# GBE1_PHY.net
KiCad netlist of a schematic drawn in Altium Designer
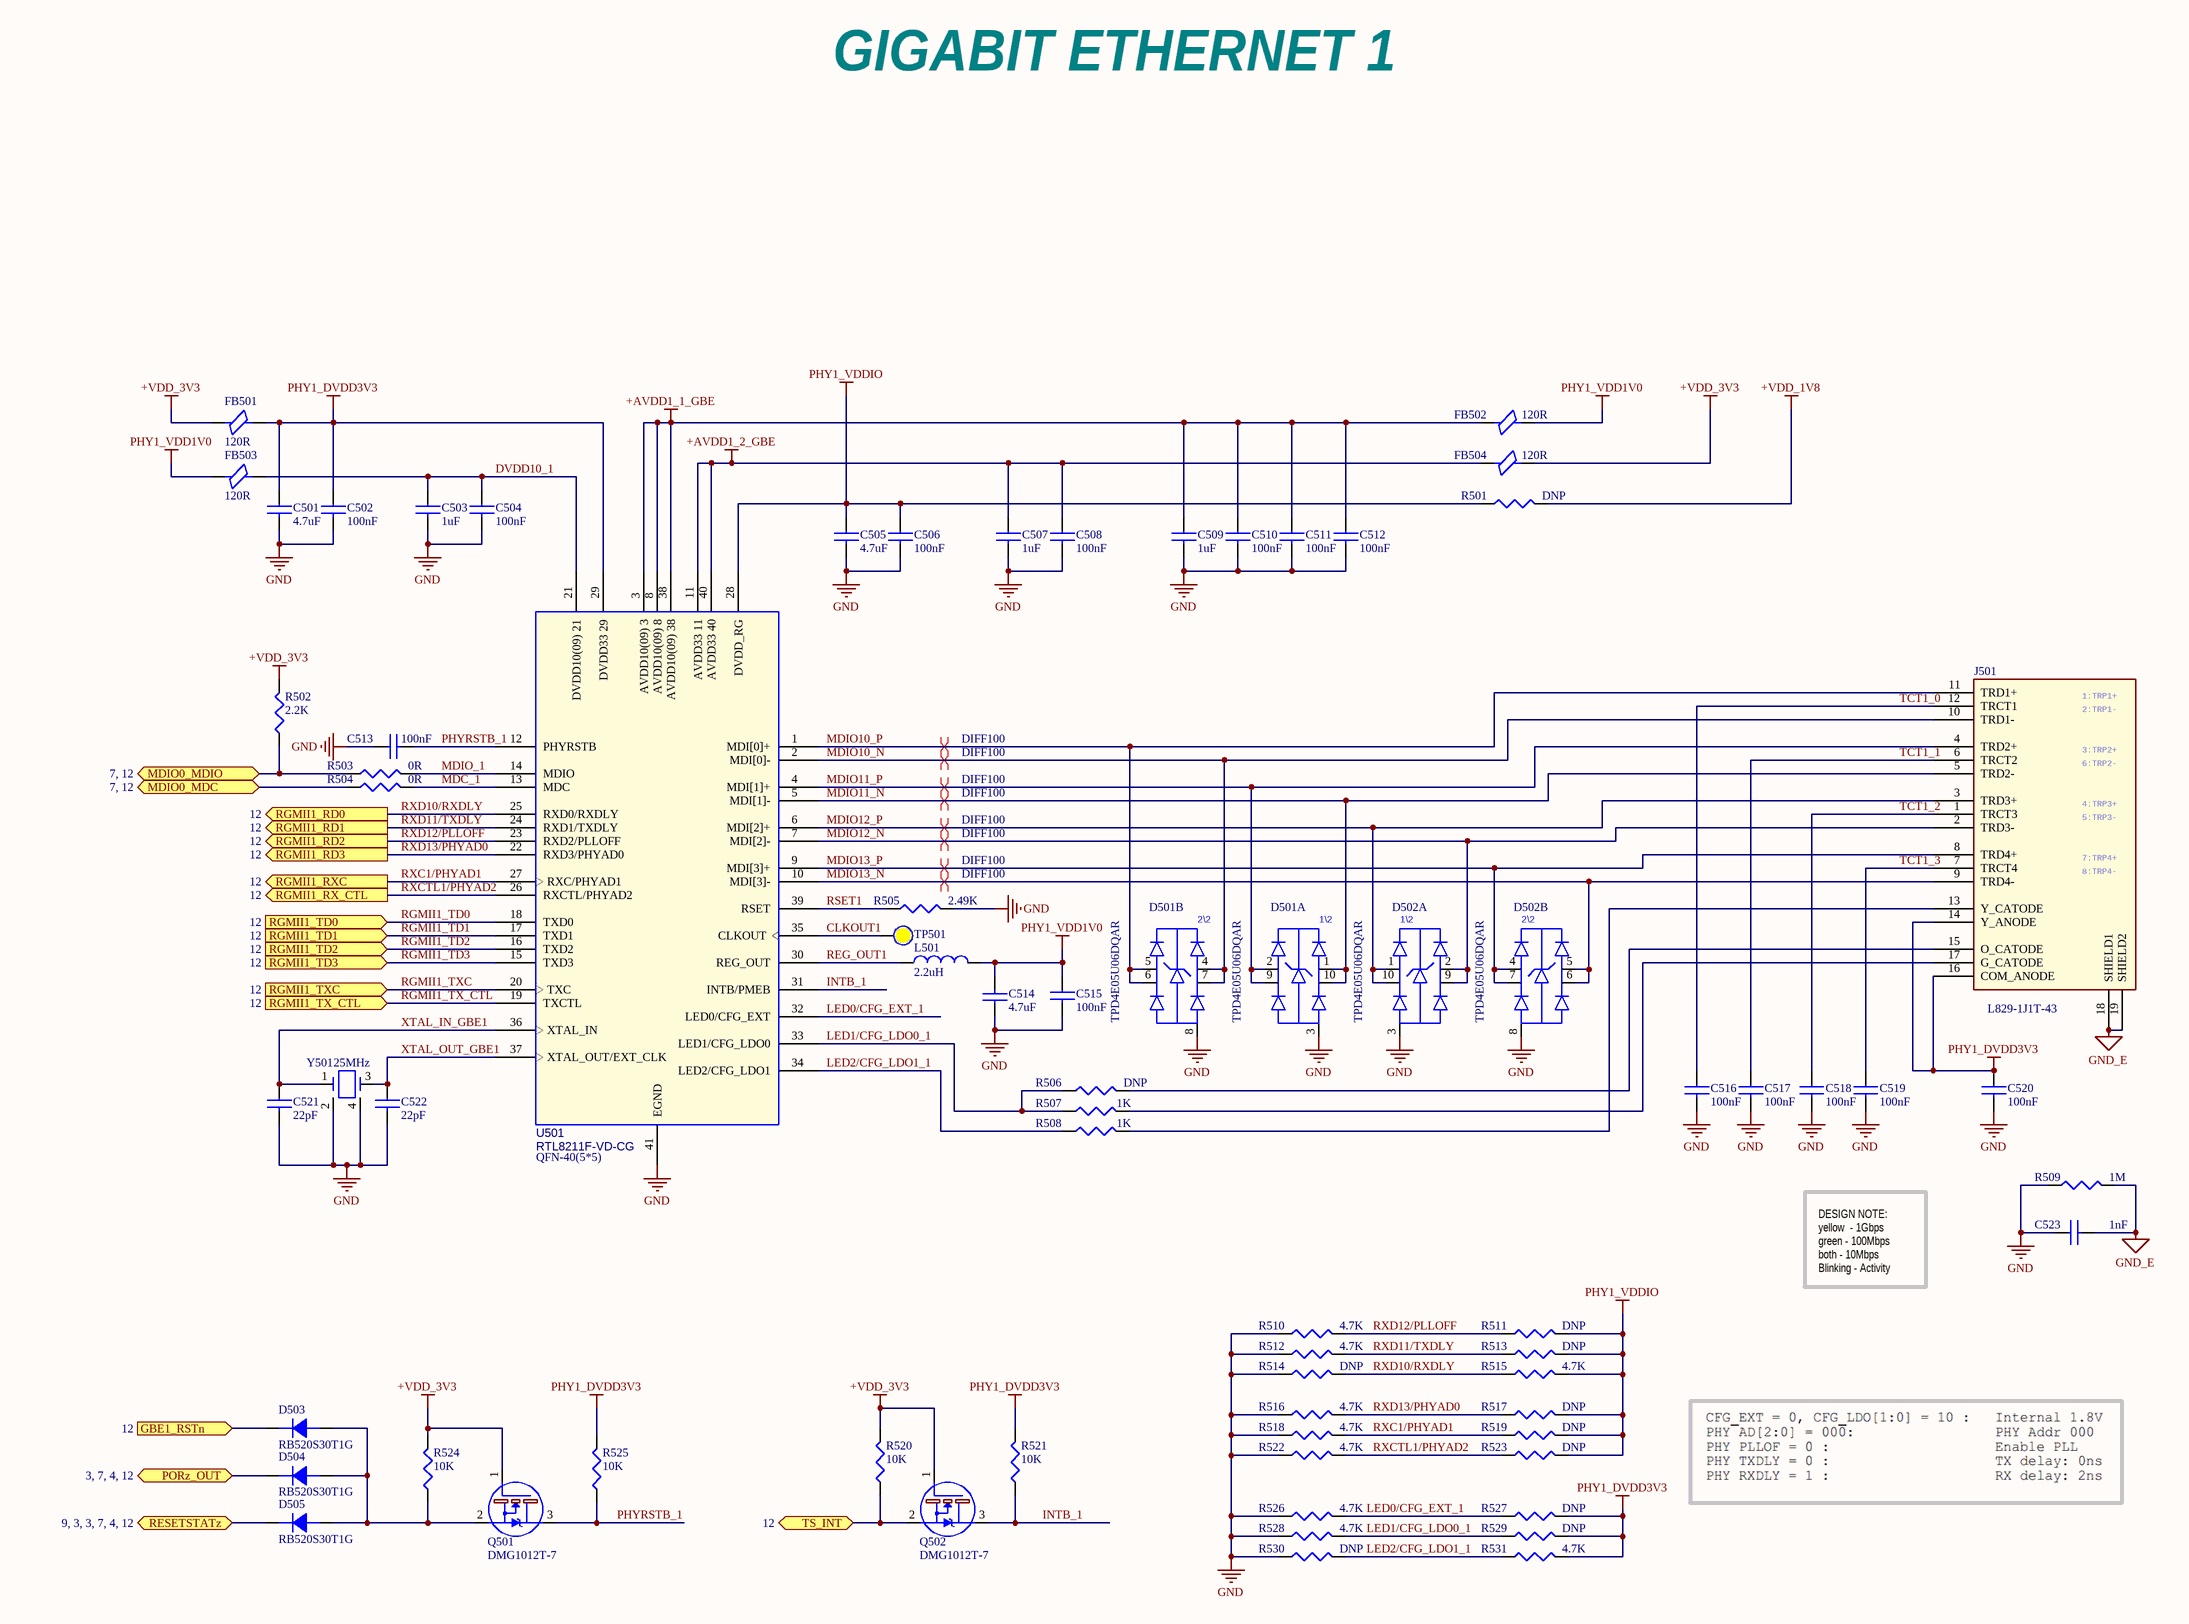
[diagram p0: GBE1 PHY.SchDoc]

(export (version "E")
  (design (tool "Eeschema 10.0.6"))
  (components
    (comp (ref "C501")
      (value "4.7uF")
      (footprint "C0402")
      (description "Multilayer Ceramic Capacitor, 4.7 uF, 6.3V, ± 10%, X5R, 0402 [1005 Metric]")
      (fields
        (field (name "MANUFACTURER") "Yageo")
        (field (name "MANUFACTURER PART NUMBER") "CC0402MRX5R5BB475")
      )
      (libsource (lib "Schlib SOM AM625") (part "CC0402MRX5R5BB475"))
    )
    (comp (ref "C502")
      (value "100nF")
      (footprint "C0201")
      (description "Multilayer Ceramic Capacitor, 0.1 uF, 16 V, ± 10%, X5R, 0201 [0603 Metric]")
      (fields
        (field (name "MANUFACTURER") "Yageo")
        (field (name "MANUFACTURER PART NUMBER") "CC0201KRX5R6BB104")
      )
      (libsource (lib "Schlib SOM AM625") (part "CC0201KRX5R6BB104"))
    )
    (comp (ref "C503")
      (value "1uF")
      (footprint "C0201")
      (description "Multilayer Ceramic Capacitor, 1 uF, 50 V, ± 0.1pF, C0G (NP0), 0201 [1005 Metric]")
      (fields
        (field (name "MANUFACTURER") "Yageo")
        (field (name "MANUFACTURER PART NUMBER") "CC0201MRX5R5BB105")
      )
      (libsource (lib "Schlib SOM AM625") (part "CC0201MRX5R5BB105"))
    )
    (comp (ref "C504")
      (value "100nF")
      (footprint "C0201")
      (description "Multilayer Ceramic Capacitor, 0.1 uF, 16 V, ± 10%, X5R, 0201 [0603 Metric]")
      (fields
        (field (name "MANUFACTURER") "Yageo")
        (field (name "MANUFACTURER PART NUMBER") "CC0201KRX5R6BB104")
      )
      (libsource (lib "Schlib SOM AM625") (part "CC0201KRX5R6BB104"))
    )
    (comp (ref "C505")
      (value "4.7uF")
      (footprint "C0402")
      (description "Multilayer Ceramic Capacitor, 4.7 uF, 6.3V, ± 10%, X5R, 0402 [1005 Metric]")
      (fields
        (field (name "MANUFACTURER") "Yageo")
        (field (name "MANUFACTURER PART NUMBER") "CC0402MRX5R5BB475")
      )
      (libsource (lib "Schlib SOM AM625") (part "CC0402MRX5R5BB475"))
    )
    (comp (ref "C506")
      (value "100nF")
      (footprint "C0201")
      (description "Multilayer Ceramic Capacitor, 0.1 uF, 16 V, ± 10%, X5R, 0201 [0603 Metric]")
      (fields
        (field (name "MANUFACTURER") "Yageo")
        (field (name "MANUFACTURER PART NUMBER") "CC0201KRX5R6BB104")
      )
      (libsource (lib "Schlib SOM AM625") (part "CC0201KRX5R6BB104"))
    )
    (comp (ref "C507")
      (value "1uF")
      (footprint "C0201")
      (description "Multilayer Ceramic Capacitor, 1 uF, 50 V, ± 0.1pF, C0G (NP0), 0201 [1005 Metric]")
      (fields
        (field (name "MANUFACTURER") "Yageo")
        (field (name "MANUFACTURER PART NUMBER") "CC0201MRX5R5BB105")
      )
      (libsource (lib "Schlib SOM AM625") (part "CC0201MRX5R5BB105"))
    )
    (comp (ref "C508")
      (value "100nF")
      (footprint "C0201")
      (description "Multilayer Ceramic Capacitor, 0.1 uF, 16 V, ± 10%, X5R, 0201 [0603 Metric]")
      (fields
        (field (name "MANUFACTURER") "Yageo")
        (field (name "MANUFACTURER PART NUMBER") "CC0201KRX5R6BB104")
      )
      (libsource (lib "Schlib SOM AM625") (part "CC0201KRX5R6BB104"))
    )
    (comp (ref "C509")
      (value "1uF")
      (footprint "C0201")
      (description "Multilayer Ceramic Capacitor, 1 uF, 50 V, ± 0.1pF, C0G (NP0), 0201 [1005 Metric]")
      (fields
        (field (name "MANUFACTURER") "Yageo")
        (field (name "MANUFACTURER PART NUMBER") "CC0201MRX5R5BB105")
      )
      (libsource (lib "Schlib SOM AM625") (part "CC0201MRX5R5BB105"))
    )
    (comp (ref "C510")
      (value "100nF")
      (footprint "C0201")
      (description "Multilayer Ceramic Capacitor, 0.1 uF, 16 V, ± 10%, X5R, 0201 [0603 Metric]")
      (fields
        (field (name "MANUFACTURER") "Yageo")
        (field (name "MANUFACTURER PART NUMBER") "CC0201KRX5R6BB104")
      )
      (libsource (lib "Schlib SOM AM625") (part "CC0201KRX5R6BB104"))
    )
    (comp (ref "C511")
      (value "100nF")
      (footprint "C0201")
      (description "Multilayer Ceramic Capacitor, 0.1 uF, 16 V, ± 10%, X5R, 0201 [0603 Metric]")
      (fields
        (field (name "MANUFACTURER") "Yageo")
        (field (name "MANUFACTURER PART NUMBER") "CC0201KRX5R6BB104")
      )
      (libsource (lib "Schlib SOM AM625") (part "CC0201KRX5R6BB104"))
    )
    (comp (ref "C512")
      (value "100nF")
      (footprint "C0201")
      (description "Multilayer Ceramic Capacitor, 0.1 uF, 16 V, ± 10%, X5R, 0201 [0603 Metric]")
      (fields
        (field (name "MANUFACTURER") "Yageo")
        (field (name "MANUFACTURER PART NUMBER") "CC0201KRX5R6BB104")
      )
      (libsource (lib "Schlib SOM AM625") (part "CC0201KRX5R6BB104"))
    )
    (comp (ref "C513")
      (value "100nF")
      (footprint "C0201")
      (description "Multilayer Ceramic Capacitor, 0.1 uF, 16 V, ± 10%, X5R, 0201 [0603 Metric]")
      (fields
        (field (name "MANUFACTURER") "Yageo")
        (field (name "MANUFACTURER PART NUMBER") "CC0201KRX5R6BB104")
      )
      (libsource (lib "Schlib SOM AM625") (part "CC0201KRX5R6BB104"))
    )
    (comp (ref "C514")
      (value "4.7uF")
      (footprint "C0402")
      (description "Multilayer Ceramic Capacitor, 4.7 uF, 6.3V, ± 10%, X5R, 0402 [1005 Metric]")
      (fields
        (field (name "MANUFACTURER") "Yageo")
        (field (name "MANUFACTURER PART NUMBER") "CC0402MRX5R5BB475")
      )
      (libsource (lib "Schlib SOM AM625") (part "CC0402MRX5R5BB475"))
    )
    (comp (ref "C515")
      (value "100nF")
      (footprint "C0201")
      (description "Multilayer Ceramic Capacitor, 0.1 uF, 16 V, ± 10%, X5R, 0201 [0603 Metric]")
      (fields
        (field (name "MANUFACTURER") "Yageo")
        (field (name "MANUFACTURER PART NUMBER") "CC0201KRX5R6BB104")
      )
      (libsource (lib "Schlib SOM AM625") (part "CC0201KRX5R6BB104"))
    )
    (comp (ref "C516")
      (value "100nF")
      (footprint "C0402")
      (description "Multilayer Ceramic Capacitor, 0.1 uF, 50 V, ± 10%, X5R, 0402 [1005 Metric]")
      (fields
        (field (name "MANUFACTURER") "TDK")
        (field (name "MANUFACTURER PART NUMBER") "C1005X5R1H104K050BB")
      )
      (libsource (lib "Schlib SOM AM625") (part "C1005X5R1H104K050BB"))
    )
    (comp (ref "C517")
      (value "100nF")
      (footprint "C0402")
      (description "Multilayer Ceramic Capacitor, 0.1 uF, 50 V, ± 10%, X5R, 0402 [1005 Metric]")
      (fields
        (field (name "MANUFACTURER") "TDK")
        (field (name "MANUFACTURER PART NUMBER") "C1005X5R1H104K050BB")
      )
      (libsource (lib "Schlib SOM AM625") (part "C1005X5R1H104K050BB"))
    )
    (comp (ref "C518")
      (value "100nF")
      (footprint "C0402")
      (description "Multilayer Ceramic Capacitor, 0.1 uF, 50 V, ± 10%, X5R, 0402 [1005 Metric]")
      (fields
        (field (name "MANUFACTURER") "TDK")
        (field (name "MANUFACTURER PART NUMBER") "C1005X5R1H104K050BB")
      )
      (libsource (lib "Schlib SOM AM625") (part "C1005X5R1H104K050BB"))
    )
    (comp (ref "C519")
      (value "100nF")
      (footprint "C0402")
      (description "Multilayer Ceramic Capacitor, 0.1 uF, 50 V, ± 10%, X5R, 0402 [1005 Metric]")
      (fields
        (field (name "MANUFACTURER") "TDK")
        (field (name "MANUFACTURER PART NUMBER") "C1005X5R1H104K050BB")
      )
      (libsource (lib "Schlib SOM AM625") (part "C1005X5R1H104K050BB"))
    )
    (comp (ref "C520")
      (value "100nF")
      (footprint "C0402")
      (description "Multilayer Ceramic Capacitor, 0.1 uF, 50 V, ± 10%, X5R, 0402 [1005 Metric]")
      (fields
        (field (name "MANUFACTURER") "TDK")
        (field (name "MANUFACTURER PART NUMBER") "C1005X5R1H104K050BB")
      )
      (libsource (lib "Schlib SOM AM625") (part "C1005X5R1H104K050BB"))
    )
    (comp (ref "C521")
      (value "22pF")
      (footprint "C0201")
      (description "0201 22 pF 50 V ±5 % Tolerance NP0 SMT Multilayer Ceramic Capacitor")
      (fields
        (field (name "MANUFACTURER") "Yageo")
        (field (name "MANUFACTURER PART NUMBER") "CC0201JRNPO9BN220")
      )
      (libsource (lib "Schlib SOM AM625") (part "CC0201JRNPO9BN220"))
    )
    (comp (ref "C522")
      (value "22pF")
      (footprint "C0201")
      (description "0201 22 pF 50 V ±5 % Tolerance NP0 SMT Multilayer Ceramic Capacitor")
      (fields
        (field (name "MANUFACTURER") "Yageo")
        (field (name "MANUFACTURER PART NUMBER") "CC0201JRNPO9BN220")
      )
      (libsource (lib "Schlib SOM AM625") (part "CC0201JRNPO9BN220"))
    )
    (comp (ref "C523")
      (value "1nF")
      (footprint "C1206B/3216MM")
      (description "Cap Ceramic 0.001uF 1000V X7R 10% Pad SMD 1206 125°C Low ESR Automotive Medical T/R")
      (fields
        (field (name "MANUFACTURER") "KEMET")
        (field (name "MANUFACTURER PART NUMBER") "C1206C102KDRACAUTO")
      )
      (libsource (lib "Schlib SOM AM625") (part "C1206C102KDRACAUTO"))
    )
    (comp (ref "D501")
      (value "TPD4E05U06DQAR")
      (footprint "10-USON")
      (description "Quad 0.5-pF, 5.5-V, ±12-kV ESD protection diode for USB, HDMI & High Speed Interfaces")
      (fields (field (name "MANUFACTURER") "Texas Instruments"))
      (libsource (lib "Schlib SOM AM625") (part "TPD4E05U06DQAR"))
    )
    (comp (ref "D502")
      (value "TPD4E05U06DQAR")
      (footprint "10-USON")
      (description "Quad 0.5-pF, 5.5-V, ±12-kV ESD protection diode for USB, HDMI & High Speed Interfaces")
      (fields (field (name "MANUFACTURER") "Texas Instruments"))
      (libsource (lib "Schlib SOM AM625") (part "TPD4E05U06DQAR"))
    )
    (comp (ref "D503")
      (value "RB520S30T1G")
      (footprint "sod_523")
      (description "Diode Schottky 30V 0.2A 2-Pin SOD-523 T/R - Product that comes on tape, but is not reeled")
      (fields (field (name "MANUFACTURER") "ON Semiconductor"))
      (libsource (lib "Schlib SOM AM625") (part "RB520S30T1G"))
    )
    (comp (ref "D504")
      (value "RB520S30T1G")
      (footprint "sod_523")
      (description "Diode Schottky 30V 0.2A 2-Pin SOD-523 T/R - Product that comes on tape, but is not reeled")
      (fields (field (name "MANUFACTURER") "ON Semiconductor"))
      (libsource (lib "Schlib SOM AM625") (part "RB520S30T1G"))
    )
    (comp (ref "D505")
      (value "RB520S30T1G")
      (footprint "sod_523")
      (description "Diode Schottky 30V 0.2A 2-Pin SOD-523 T/R - Product that comes on tape, but is not reeled")
      (fields (field (name "MANUFACTURER") "ON Semiconductor"))
      (libsource (lib "Schlib SOM AM625") (part "RB520S30T1G"))
    )
    (comp (ref "FB501")
      (value "120R")
      (footprint "FB0402")
      (description "Ferrite Beads Multi-Layer 120Ohm 25% 100MHz 1.3A 0.09Ohm DCR 0402 Automotive T/R")
      (fields
        (field (name "MANUFACTURER") "Murata")
        (field (name "MANUFACTURER PART NUMBER") "BLM15PD121SZ1D")
      )
      (libsource (lib "Schlib SOM AM625") (part "BLM15PD121SZ1D"))
    )
    (comp (ref "FB502")
      (value "120R")
      (footprint "FB0402")
      (description "Ferrite Beads Multi-Layer 120Ohm 25% 100MHz 1.3A 0.09Ohm DCR 0402 Automotive T/R")
      (fields
        (field (name "MANUFACTURER") "Murata")
        (field (name "MANUFACTURER PART NUMBER") "BLM15PD121SZ1D")
      )
      (libsource (lib "Schlib SOM AM625") (part "BLM15PD121SZ1D"))
    )
    (comp (ref "FB503")
      (value "120R")
      (footprint "FB0402")
      (description "Ferrite Beads Multi-Layer 120Ohm 25% 100MHz 1.3A 0.09Ohm DCR 0402 Automotive T/R")
      (fields
        (field (name "MANUFACTURER") "Murata")
        (field (name "MANUFACTURER PART NUMBER") "BLM15PD121SZ1D")
      )
      (libsource (lib "Schlib SOM AM625") (part "BLM15PD121SZ1D"))
    )
    (comp (ref "FB504")
      (value "120R")
      (footprint "FB0402")
      (description "Ferrite Beads Multi-Layer 120Ohm 25% 100MHz 1.3A 0.09Ohm DCR 0402 Automotive T/R")
      (fields
        (field (name "MANUFACTURER") "Murata")
        (field (name "MANUFACTURER PART NUMBER") "BLM15PD121SZ1D")
      )
      (libsource (lib "Schlib SOM AM625") (part "BLM15PD121SZ1D"))
    )
    (comp (ref "J501")
      (value "L829-1J1T-43")
      (footprint "L829-1J1T-43")
      (description "CONN MAGJACK 1PORT SHLD 1000BT")
      (fields
        (field (name "MANUFACTURER") "Bel Fuse Inc")
        (field (name ".CHECKED PCB") "RF")
        (field (name ".CHECKED SCH") "RF")
      )
      (libsource (lib "Schlib SOM AM625") (part "L829-1J1T-43"))
    )
    (comp (ref "L501")
      (value "2.2uH")
      (footprint "l2016")
      (description "Inductor Power Shielded Wirewound 2.2uH 20% 1MHz Metal 1.4A 0.168Ohm DCR 0806 T/R")
      (fields
        (field (name "MANUFACTURER") "Murata")
        (field (name "MANUFACTURER PART NUMBER") "DFE201610P-2R2M=P2")
      )
      (libsource (lib "Schlib SOM AM625") (part "DFE201610P-2R2M=P2"))
    )
    (comp (ref "Q501")
      (value "DMG1012T-7")
      (footprint "sot_523")
      (description "Transistor MOSFET NTR4003NT1G, SOT23, ON Semi")
      (fields (field (name "MANUFACTURER") "Diodes"))
      (libsource (lib "Schlib SOM AM625") (part "DMG1012T-7"))
    )
    (comp (ref "Q502")
      (value "DMG1012T-7")
      (footprint "sot_523")
      (description "Transistor MOSFET NTR4003NT1G, SOT23, ON Semi")
      (fields (field (name "MANUFACTURER") "Diodes"))
      (libsource (lib "Schlib SOM AM625") (part "DMG1012T-7"))
    )
    (comp (ref "R501")
      (value "DNP")
      (footprint "R0402")
      (description "Zero Ohm Resistor, Jumper, 0402 [1005 Metric], Thick Film, 63 mW, 1 A, Surface Mount")
      (fields
        (field (name "MANUFACTURER") "Yageo")
        (field (name "MANUFACTURER PART NUMBER") "RC0402JR-070RL")
      )
      (libsource (lib "Schlib SOM AM625") (part "RC0402JR-070RL"))
    )
    (comp (ref "R502")
      (value "2.2K")
      (footprint "R0201")
      (description "SMD Chip Resistor, 2.2 kOhm, ± 1%, 50 mW, 0201 [0603 Metric], Thick Film, General Purpose")
      (fields
        (field (name "MANUFACTURER") "Yageo")
        (field (name "MANUFACTURER PART NUMBER") "RC0201FR-072K2L")
      )
      (libsource (lib "Schlib SOM AM625") (part "RC0201FR-072K2L"))
    )
    (comp (ref "R503")
      (value "0R")
      (footprint "R0201")
      (description "Zero Ohm Resistor, Jumper, 0201 [0603 Metric], Thick Film, 50 mW, 500 mA, Surface Mount")
      (fields
        (field (name "MANUFACTURER") "Yageo")
        (field (name "MANUFACTURER PART NUMBER") "RC0201JR-070RL")
      )
      (libsource (lib "Schlib SOM AM625") (part "RC0201JR-070RL"))
    )
    (comp (ref "R504")
      (value "0R")
      (footprint "R0201")
      (description "Zero Ohm Resistor, Jumper, 0201 [0603 Metric], Thick Film, 50 mW, 500 mA, Surface Mount")
      (fields
        (field (name "MANUFACTURER") "Yageo")
        (field (name "MANUFACTURER PART NUMBER") "RC0201JR-070RL")
      )
      (libsource (lib "Schlib SOM AM625") (part "RC0201JR-070RL"))
    )
    (comp (ref "R505")
      (value "2.49K")
      (footprint "R0201")
      (description "SMD Chip Resistor, 2.49 kOhm, ± 1%, 50 mW, 0201 [0603 Metric], Thick Film, General Purpose")
      (fields
        (field (name "MANUFACTURER") "Yageo")
        (field (name "MANUFACTURER PART NUMBER") "RC0201FR-072K49L")
      )
      (libsource (lib "Schlib SOM AM625") (part "RC0201FR-072K49L"))
    )
    (comp (ref "R506")
      (value "DNP")
      (footprint "R0402")
      (description "Zero Ohm Resistor, Jumper, 0402 [1005 Metric], Thick Film, 63 mW, 1 A, Surface Mount")
      (fields
        (field (name "MANUFACTURER") "Yageo")
        (field (name "MANUFACTURER PART NUMBER") "RC0402JR-070RL")
      )
      (libsource (lib "Schlib SOM AM625") (part "RC0402JR-070RL"))
    )
    (comp (ref "R507")
      (value "1K")
      (footprint "R0402")
      (description "SMD Chip Resistor, 1 kOhm, ± 1%, 63 mW, 0402 [1005 Metric], Thick Film, General Purpose")
      (fields
        (field (name "MANUFACTURER") "Yageo")
        (field (name "MANUFACTURER PART NUMBER") "RC0402FR-071KL")
      )
      (libsource (lib "Schlib SOM AM625") (part "RC0402FR-071KL"))
    )
    (comp (ref "R508")
      (value "1K")
      (footprint "R0402")
      (description "SMD Chip Resistor, 1 kOhm, ± 1%, 63 mW, 0402 [1005 Metric], Thick Film, General Purpose")
      (fields
        (field (name "MANUFACTURER") "Yageo")
        (field (name "MANUFACTURER PART NUMBER") "RC0402FR-071KL")
      )
      (libsource (lib "Schlib SOM AM625") (part "RC0402FR-071KL"))
    )
    (comp (ref "R509")
      (value "1M")
      (footprint "R1206B/3216MM")
      (description "SMD Chip Resistor, 1 MOhm, ± 1%, 250 mW, 1206 [3216 Metric], Thick Film, General Purpose")
      (fields
        (field (name "MANUFACTURER") "Yageo")
        (field (name "MANUFACTURER PART NUMBER") "RC1206FR-071ML")
      )
      (libsource (lib "Schlib SOM AM625") (part "RC1206FR-071ML"))
    )
    (comp (ref "R510")
      (value "4.7K")
      (footprint "R0201")
      (description "SMD Chip Resistor, 4.7 kOhm, ± 5%, 50 mW, 0201 [0603 Metric], Thick Film, General Purpose")
      (fields
        (field (name "MANUFACTURER") "Yageo")
        (field (name "MANUFACTURER PART NUMBER") "RC0201JR-074K7L")
      )
      (libsource (lib "Schlib SOM AM625") (part "RC0201JR-074K7L"))
    )
    (comp (ref "R511")
      (value "DNP")
      (footprint "R0201")
      (description "SMD Chip Resistor, 4.7 kOhm, ± 5%, 50 mW, 0201 [0603 Metric], Thick Film, General Purpose")
      (fields
        (field (name "MANUFACTURER") "Yageo")
        (field (name "MANUFACTURER PART NUMBER") "RC0201JR-074K7L")
      )
      (libsource (lib "Schlib SOM AM625") (part "RC0201JR-074K7L"))
    )
    (comp (ref "R512")
      (value "4.7K")
      (footprint "R0201")
      (description "SMD Chip Resistor, 4.7 kOhm, ± 5%, 50 mW, 0201 [0603 Metric], Thick Film, General Purpose")
      (fields
        (field (name "MANUFACTURER") "Yageo")
        (field (name "MANUFACTURER PART NUMBER") "RC0201JR-074K7L")
      )
      (libsource (lib "Schlib SOM AM625") (part "RC0201JR-074K7L"))
    )
    (comp (ref "R513")
      (value "DNP")
      (footprint "R0201")
      (description "SMD Chip Resistor, 4.7 kOhm, ± 5%, 50 mW, 0201 [0603 Metric], Thick Film, General Purpose")
      (fields
        (field (name "MANUFACTURER") "Yageo")
        (field (name "MANUFACTURER PART NUMBER") "RC0201JR-074K7L")
      )
      (libsource (lib "Schlib SOM AM625") (part "RC0201JR-074K7L"))
    )
    (comp (ref "R514")
      (value "DNP")
      (footprint "R0201")
      (description "SMD Chip Resistor, 4.7 kOhm, ± 5%, 50 mW, 0201 [0603 Metric], Thick Film, General Purpose")
      (fields
        (field (name "MANUFACTURER") "Yageo")
        (field (name "MANUFACTURER PART NUMBER") "RC0201JR-074K7L")
      )
      (libsource (lib "Schlib SOM AM625") (part "RC0201JR-074K7L"))
    )
    (comp (ref "R515")
      (value "4.7K")
      (footprint "R0201")
      (description "SMD Chip Resistor, 4.7 kOhm, ± 5%, 50 mW, 0201 [0603 Metric], Thick Film, General Purpose")
      (fields
        (field (name "MANUFACTURER") "Yageo")
        (field (name "MANUFACTURER PART NUMBER") "RC0201JR-074K7L")
      )
      (libsource (lib "Schlib SOM AM625") (part "RC0201JR-074K7L"))
    )
    (comp (ref "R516")
      (value "4.7K")
      (footprint "R0201")
      (description "SMD Chip Resistor, 4.7 kOhm, ± 5%, 50 mW, 0201 [0603 Metric], Thick Film, General Purpose")
      (fields
        (field (name "MANUFACTURER") "Yageo")
        (field (name "MANUFACTURER PART NUMBER") "RC0201JR-074K7L")
      )
      (libsource (lib "Schlib SOM AM625") (part "RC0201JR-074K7L"))
    )
    (comp (ref "R517")
      (value "DNP")
      (footprint "R0201")
      (description "SMD Chip Resistor, 4.7 kOhm, ± 5%, 50 mW, 0201 [0603 Metric], Thick Film, General Purpose")
      (fields
        (field (name "MANUFACTURER") "Yageo")
        (field (name "MANUFACTURER PART NUMBER") "RC0201JR-074K7L")
      )
      (libsource (lib "Schlib SOM AM625") (part "RC0201JR-074K7L"))
    )
    (comp (ref "R518")
      (value "4.7K")
      (footprint "R0201")
      (description "SMD Chip Resistor, 4.7 kOhm, ± 5%, 50 mW, 0201 [0603 Metric], Thick Film, General Purpose")
      (fields
        (field (name "MANUFACTURER") "Yageo")
        (field (name "MANUFACTURER PART NUMBER") "RC0201JR-074K7L")
      )
      (libsource (lib "Schlib SOM AM625") (part "RC0201JR-074K7L"))
    )
    (comp (ref "R519")
      (value "DNP")
      (footprint "R0201")
      (description "SMD Chip Resistor, 4.7 kOhm, ± 5%, 50 mW, 0201 [0603 Metric], Thick Film, General Purpose")
      (fields
        (field (name "MANUFACTURER") "Yageo")
        (field (name "MANUFACTURER PART NUMBER") "RC0201JR-074K7L")
      )
      (libsource (lib "Schlib SOM AM625") (part "RC0201JR-074K7L"))
    )
    (comp (ref "R520")
      (value "10K")
      (footprint "R0201")
      (description "SMD Chip Resistor, 10 kOhm, ± 1%, 50 mW, 0201 [0603 Metric], Thick Film, General Purpose")
      (fields
        (field (name "MANUFACTURER") "Yageo")
        (field (name "MANUFACTURER PART NUMBER") "RC0201FR-0710KL")
      )
      (libsource (lib "Schlib SOM AM625") (part "RC0201FR-0710KL"))
    )
    (comp (ref "R521")
      (value "10K")
      (footprint "R0201")
      (description "SMD Chip Resistor, 10 kOhm, ± 1%, 50 mW, 0201 [0603 Metric], Thick Film, General Purpose")
      (fields
        (field (name "MANUFACTURER") "Yageo")
        (field (name "MANUFACTURER PART NUMBER") "RC0201FR-0710KL")
      )
      (libsource (lib "Schlib SOM AM625") (part "RC0201FR-0710KL"))
    )
    (comp (ref "R522")
      (value "4.7K")
      (footprint "R0201")
      (description "SMD Chip Resistor, 4.7 kOhm, ± 5%, 50 mW, 0201 [0603 Metric], Thick Film, General Purpose")
      (fields
        (field (name "MANUFACTURER") "Yageo")
        (field (name "MANUFACTURER PART NUMBER") "RC0201JR-074K7L")
      )
      (libsource (lib "Schlib SOM AM625") (part "RC0201JR-074K7L"))
    )
    (comp (ref "R523")
      (value "DNP")
      (footprint "R0201")
      (description "SMD Chip Resistor, 4.7 kOhm, ± 5%, 50 mW, 0201 [0603 Metric], Thick Film, General Purpose")
      (fields
        (field (name "MANUFACTURER") "Yageo")
        (field (name "MANUFACTURER PART NUMBER") "RC0201JR-074K7L")
      )
      (libsource (lib "Schlib SOM AM625") (part "RC0201JR-074K7L"))
    )
    (comp (ref "R524")
      (value "10K")
      (footprint "R0201")
      (description "SMD Chip Resistor, 10 kOhm, ± 1%, 50 mW, 0201 [0603 Metric], Thick Film, General Purpose")
      (fields
        (field (name "MANUFACTURER") "Yageo")
        (field (name "MANUFACTURER PART NUMBER") "RC0201FR-0710KL")
      )
      (libsource (lib "Schlib SOM AM625") (part "RC0201FR-0710KL"))
    )
    (comp (ref "R525")
      (value "10K")
      (footprint "R0201")
      (description "SMD Chip Resistor, 10 kOhm, ± 1%, 50 mW, 0201 [0603 Metric], Thick Film, General Purpose")
      (fields
        (field (name "MANUFACTURER") "Yageo")
        (field (name "MANUFACTURER PART NUMBER") "RC0201FR-0710KL")
      )
      (libsource (lib "Schlib SOM AM625") (part "RC0201FR-0710KL"))
    )
    (comp (ref "R526")
      (value "4.7K")
      (footprint "R0201")
      (description "SMD Chip Resistor, 4.7 kOhm, ± 5%, 50 mW, 0201 [0603 Metric], Thick Film, General Purpose")
      (fields
        (field (name "MANUFACTURER") "Yageo")
        (field (name "MANUFACTURER PART NUMBER") "RC0201JR-074K7L")
      )
      (libsource (lib "Schlib SOM AM625") (part "RC0201JR-074K7L"))
    )
    (comp (ref "R527")
      (value "DNP")
      (footprint "R0201")
      (description "SMD Chip Resistor, 4.7 kOhm, ± 5%, 50 mW, 0201 [0603 Metric], Thick Film, General Purpose")
      (fields
        (field (name "MANUFACTURER") "Yageo")
        (field (name "MANUFACTURER PART NUMBER") "RC0201JR-074K7L")
      )
      (libsource (lib "Schlib SOM AM625") (part "RC0201JR-074K7L"))
    )
    (comp (ref "R528")
      (value "4.7K")
      (footprint "R0201")
      (description "SMD Chip Resistor, 4.7 kOhm, ± 5%, 50 mW, 0201 [0603 Metric], Thick Film, General Purpose")
      (fields
        (field (name "MANUFACTURER") "Yageo")
        (field (name "MANUFACTURER PART NUMBER") "RC0201JR-074K7L")
      )
      (libsource (lib "Schlib SOM AM625") (part "RC0201JR-074K7L"))
    )
    (comp (ref "R529")
      (value "DNP")
      (footprint "R0201")
      (description "SMD Chip Resistor, 4.7 kOhm, ± 5%, 50 mW, 0201 [0603 Metric], Thick Film, General Purpose")
      (fields
        (field (name "MANUFACTURER") "Yageo")
        (field (name "MANUFACTURER PART NUMBER") "RC0201JR-074K7L")
      )
      (libsource (lib "Schlib SOM AM625") (part "RC0201JR-074K7L"))
    )
    (comp (ref "R530")
      (value "DNP")
      (footprint "R0201")
      (description "SMD Chip Resistor, 4.7 kOhm, ± 5%, 50 mW, 0201 [0603 Metric], Thick Film, General Purpose")
      (fields
        (field (name "MANUFACTURER") "Yageo")
        (field (name "MANUFACTURER PART NUMBER") "RC0201JR-074K7L")
      )
      (libsource (lib "Schlib SOM AM625") (part "RC0201JR-074K7L"))
    )
    (comp (ref "R531")
      (value "4.7K")
      (footprint "R0201")
      (description "SMD Chip Resistor, 4.7 kOhm, ± 5%, 50 mW, 0201 [0603 Metric], Thick Film, General Purpose")
      (fields
        (field (name "MANUFACTURER") "Yageo")
        (field (name "MANUFACTURER PART NUMBER") "RC0201JR-074K7L")
      )
      (libsource (lib "Schlib SOM AM625") (part "RC0201JR-074K7L"))
    )
    (comp (ref "TP501")
      (value "~")
      (footprint "Test Point 1 MM")
      (description "Test Point")
      (libsource (lib "BYTECH_HW_LIB_2019") (part "Test Point"))
    )
    (comp (ref "U501")
      (value "RTL8211F-VD-CG")
      (footprint "qfn40_0D4_5x5mm")
      (description "IC, Interface, Ethernet, RTL8211F-VD-CG, QFN-40(5*5)")
      (fields
        (field (name "MANUFACTURER") "Realtek")
        (field (name "PACKAGE SIZE") "QFN-40(5*5)")
        (field (name "Comment") "RTL8211")
      )
      (libsource (lib "Schlib SOM AM625") (part "RTL8211"))
    )
    (comp (ref "Y501")
      (value "25MHz")
      (footprint "x4-smd-3_2x2_5x1_0mm")
      (description "Crystal, 25MHZ, 18PF, SMD")
      (fields (field (name "MANUFACTURER") "IQD") (field (name "MANUFACTURER PART NUMBER") "LFXTAL055299"))
      (libsource (lib "Schlib SOM AM625") (part "LFXTAL055299"))
    )
  )
  (nets
    (net (code "1") (name "+AVDD1_1_GBE") (class "Default")
      (node (ref "C509") (pin "1") (pinfunction "1_1") (pintype "passive"))
      (node (ref "C510") (pin "1") (pinfunction "1_1") (pintype "passive"))
      (node (ref "C511") (pin "1") (pinfunction "1_1") (pintype "passive"))
      (node (ref "C512") (pin "1") (pinfunction "1_1") (pintype "passive"))
      (node (ref "FB502") (pin "1") (pinfunction "1_1") (pintype "passive"))
      (node (ref "U501") (pin "3") (pinfunction "AVDD10(09)_3_3") (pintype "power_in"))
      (node (ref "U501") (pin "38") (pinfunction "AVDD10(09)_38_38") (pintype "power_in"))
      (node (ref "U501") (pin "8") (pinfunction "AVDD10(09)_8_8") (pintype "power_in"))
    )
    (net (code "2") (name "+AVDD1_2_GBE") (class "Default")
      (node (ref "C507") (pin "1") (pinfunction "1_1") (pintype "passive"))
      (node (ref "C508") (pin "1") (pinfunction "1_1") (pintype "passive"))
      (node (ref "FB504") (pin "1") (pinfunction "1_1") (pintype "passive"))
      (node (ref "U501") (pin "11") (pinfunction "AVDD33_11_11") (pintype "power_in"))
      (node (ref "U501") (pin "40") (pinfunction "AVDD33_40_40") (pintype "power_in"))
    )
    (net (code "3") (name "+VDD_1V8") (class "Default")
      (node (ref "R501") (pin "2") (pinfunction "2_2") (pintype "passive"))
    )
    (net (code "4") (name "+VDD_3V3") (class "Default")
      (node (ref "FB501") (pin "1") (pinfunction "1_1") (pintype "passive"))
      (node (ref "FB504") (pin "2") (pinfunction "2_2") (pintype "passive"))
      (node (ref "Q501") (pin "1") (pinfunction "G_1") (pintype "passive"))
      (node (ref "Q502") (pin "1") (pinfunction "G_1") (pintype "passive"))
      (node (ref "R502") (pin "2") (pinfunction "2_2") (pintype "passive"))
      (node (ref "R520") (pin "2") (pinfunction "2_2") (pintype "passive"))
      (node (ref "R524") (pin "2") (pinfunction "2_2") (pintype "passive"))
    )
    (net (code "5") (name "/CLKOUT1") (class "Default")
      (node (ref "TP501") (pin "0") (pinfunction "0_0") (pintype "passive"))
      (node (ref "U501") (pin "35") (pinfunction "CLKOUT_35") (pintype "passive"))
    )
    (net (code "6") (name "/DVDD10_1") (class "Default")
      (node (ref "C503") (pin "1") (pinfunction "1_1") (pintype "passive"))
      (node (ref "C504") (pin "1") (pinfunction "1_1") (pintype "passive"))
      (node (ref "FB503") (pin "2") (pinfunction "2_2") (pintype "passive"))
      (node (ref "U501") (pin "21") (pinfunction "DVDD10(09)_21_21") (pintype "power_in"))
    )
    (net (code "7") (name "/GBE1_RSTn") (class "Default")
      (node (ref "D503") (pin "2") (pinfunction "C_2") (pintype "passive"))
    )
    (net (code "8") (name "/INTB_1") (class "Default")
      (node (ref "Q502") (pin "3") (pinfunction "D_3") (pintype "passive"))
      (node (ref "R521") (pin "1") (pinfunction "1_1") (pintype "passive"))
      (node (ref "U501") (pin "31") (pinfunction "INTB/PMEB_31") (pintype "passive"))
    )
    (net (code "9") (name "/LED0{slash}CFG_EXT_1") (class "Default")
      (node (ref "R526") (pin "2") (pinfunction "2_2") (pintype "passive"))
      (node (ref "R527") (pin "1") (pinfunction "1_1") (pintype "passive"))
      (node (ref "U501") (pin "32") (pinfunction "LED0/CFG_EXT_32") (pintype "passive"))
    )
    (net (code "10") (name "/LED1{slash}CFG_LDO0_1") (class "Default")
      (node (ref "R506") (pin "1") (pinfunction "1_1") (pintype "passive"))
      (node (ref "R507") (pin "1") (pinfunction "1_1") (pintype "passive"))
      (node (ref "R528") (pin "2") (pinfunction "2_2") (pintype "passive"))
      (node (ref "R529") (pin "1") (pinfunction "1_1") (pintype "passive"))
      (node (ref "U501") (pin "33") (pinfunction "LED1/CFG_LDO0_33") (pintype "passive"))
    )
    (net (code "11") (name "/LED2{slash}CFG_LDO1_1") (class "Default")
      (node (ref "R508") (pin "1") (pinfunction "1_1") (pintype "passive"))
      (node (ref "R530") (pin "2") (pinfunction "2_2") (pintype "passive"))
      (node (ref "R531") (pin "1") (pinfunction "1_1") (pintype "passive"))
      (node (ref "U501") (pin "34") (pinfunction "LED2/CFG_LDO1_34") (pintype "passive"))
    )
    (net (code "12") (name "/MDC_1") (class "Default")
      (node (ref "R504") (pin "2") (pinfunction "2_2") (pintype "passive"))
      (node (ref "U501") (pin "13") (pinfunction "MDC_13") (pintype "passive"))
    )
    (net (code "13") (name "/MDIO0_MDC") (class "Default")
      (node (ref "R504") (pin "1") (pinfunction "1_1") (pintype "passive"))
    )
    (net (code "14") (name "/MDIO0_MDIO") (class "Default")
      (node (ref "R502") (pin "1") (pinfunction "1_1") (pintype "passive"))
      (node (ref "R503") (pin "1") (pinfunction "1_1") (pintype "passive"))
    )
    (net (code "15") (name "/MDIO10_N") (class "Default")
      (node (ref "D501") (pin "4") (pinfunction "3A_4") (pintype "passive"))
      (node (ref "D501") (pin "7") (pinfunction "3B_7") (pintype "passive"))
      (node (ref "J501") (pin "10") (pinfunction "TRD1-_10") (pintype "passive"))
      (node (ref "U501") (pin "2") (pinfunction "MDI[0]-_2") (pintype "passive"))
    )
    (net (code "16") (name "/MDIO10_P") (class "Default")
      (node (ref "D501") (pin "5") (pinfunction "4A_5") (pintype "passive"))
      (node (ref "D501") (pin "6") (pinfunction "4B_6") (pintype "passive"))
      (node (ref "J501") (pin "11") (pinfunction "TRD1+_11") (pintype "passive"))
      (node (ref "U501") (pin "1") (pinfunction "MDI[0]+_1") (pintype "passive"))
    )
    (net (code "17") (name "/MDIO11_N") (class "Default")
      (node (ref "D501") (pin "1") (pinfunction "1A_1") (pintype "passive"))
      (node (ref "D501") (pin "10") (pinfunction "1B_10") (pintype "passive"))
      (node (ref "J501") (pin "5") (pinfunction "TRD2-_5") (pintype "passive"))
      (node (ref "U501") (pin "5") (pinfunction "MDI[1]-_5") (pintype "passive"))
    )
    (net (code "18") (name "/MDIO11_P") (class "Default")
      (node (ref "D501") (pin "2") (pinfunction "2A_2") (pintype "passive"))
      (node (ref "D501") (pin "9") (pinfunction "2B_9") (pintype "passive"))
      (node (ref "J501") (pin "4") (pinfunction "TRD2+_4") (pintype "passive"))
      (node (ref "U501") (pin "4") (pinfunction "MDI[1]+_4") (pintype "passive"))
    )
    (net (code "19") (name "/MDIO12_N") (class "Default")
      (node (ref "D502") (pin "2") (pinfunction "2A_2") (pintype "passive"))
      (node (ref "D502") (pin "9") (pinfunction "2B_9") (pintype "passive"))
      (node (ref "J501") (pin "2") (pinfunction "TRD3-_2") (pintype "passive"))
      (node (ref "U501") (pin "7") (pinfunction "MDI[2]-_7") (pintype "passive"))
    )
    (net (code "20") (name "/MDIO12_P") (class "Default")
      (node (ref "D502") (pin "1") (pinfunction "1A_1") (pintype "passive"))
      (node (ref "D502") (pin "10") (pinfunction "1B_10") (pintype "passive"))
      (node (ref "J501") (pin "3") (pinfunction "TRD3+_3") (pintype "passive"))
      (node (ref "U501") (pin "6") (pinfunction "MDI[2]+_6") (pintype "passive"))
    )
    (net (code "21") (name "/MDIO13_N") (class "Default")
      (node (ref "D502") (pin "5") (pinfunction "4A_5") (pintype "passive"))
      (node (ref "D502") (pin "6") (pinfunction "4B_6") (pintype "passive"))
      (node (ref "J501") (pin "9") (pinfunction "TRD4-_9") (pintype "passive"))
      (node (ref "U501") (pin "10") (pinfunction "MDI[3]-_10") (pintype "passive"))
    )
    (net (code "22") (name "/MDIO13_P") (class "Default")
      (node (ref "D502") (pin "4") (pinfunction "3A_4") (pintype "passive"))
      (node (ref "D502") (pin "7") (pinfunction "3B_7") (pintype "passive"))
      (node (ref "J501") (pin "8") (pinfunction "TRD4+_8") (pintype "passive"))
      (node (ref "U501") (pin "9") (pinfunction "MDI[3]+_9") (pintype "passive"))
    )
    (net (code "23") (name "/MDIO_1") (class "Default")
      (node (ref "R503") (pin "2") (pinfunction "2_2") (pintype "passive"))
      (node (ref "U501") (pin "14") (pinfunction "MDIO_14") (pintype "passive"))
    )
    (net (code "24") (name "/PHYRSTB_1") (class "Default")
      (node (ref "C513") (pin "2") (pinfunction "2_2") (pintype "passive"))
      (node (ref "Q501") (pin "3") (pinfunction "D_3") (pintype "passive"))
      (node (ref "R525") (pin "1") (pinfunction "1_1") (pintype "passive"))
      (node (ref "U501") (pin "12") (pinfunction "PHYRSTB_12") (pintype "passive"))
    )
    (net (code "25") (name "/PORz_OUT") (class "Default")
      (node (ref "D504") (pin "2") (pinfunction "C_2") (pintype "passive"))
    )
    (net (code "26") (name "/REG_OUT1") (class "Default")
      (node (ref "L501") (pin "1") (pinfunction "1_1") (pintype "passive"))
      (node (ref "U501") (pin "30") (pinfunction "REG_OUT_30") (pintype "power_in"))
    )
    (net (code "27") (name "/RESETSTATz") (class "Default")
      (node (ref "D505") (pin "2") (pinfunction "C_2") (pintype "passive"))
    )
    (net (code "28") (name "/RGMII1_TD0") (class "Default")
      (node (ref "U501") (pin "18") (pinfunction "TXD0_18") (pintype "passive"))
    )
    (net (code "29") (name "/RGMII1_TD1") (class "Default")
      (node (ref "U501") (pin "17") (pinfunction "TXD1_17") (pintype "passive"))
    )
    (net (code "30") (name "/RGMII1_TD2") (class "Default")
      (node (ref "U501") (pin "16") (pinfunction "TXD2_16") (pintype "passive"))
    )
    (net (code "31") (name "/RGMII1_TD3") (class "Default")
      (node (ref "U501") (pin "15") (pinfunction "TXD3_15") (pintype "passive"))
    )
    (net (code "32") (name "/RGMII1_TXC") (class "Default")
      (node (ref "U501") (pin "20") (pinfunction "TXC_20") (pintype "passive"))
    )
    (net (code "33") (name "/RGMII1_TX_CTL") (class "Default")
      (node (ref "U501") (pin "19") (pinfunction "TXCTL_19") (pintype "passive"))
    )
    (net (code "34") (name "/RSET1") (class "Default")
      (node (ref "R505") (pin "1") (pinfunction "1_1") (pintype "passive"))
      (node (ref "U501") (pin "39") (pinfunction "RSET_39") (pintype "passive"))
    )
    (net (code "35") (name "/RXC1{slash}PHYAD1") (class "Default")
      (node (ref "R518") (pin "2") (pinfunction "2_2") (pintype "passive"))
      (node (ref "R519") (pin "1") (pinfunction "1_1") (pintype "passive"))
      (node (ref "U501") (pin "27") (pinfunction "RXC/PHYAD1_27") (pintype "passive"))
    )
    (net (code "36") (name "/RXCTL1{slash}PHYAD2") (class "Default")
      (node (ref "R522") (pin "2") (pinfunction "2_2") (pintype "passive"))
      (node (ref "R523") (pin "1") (pinfunction "1_1") (pintype "passive"))
      (node (ref "U501") (pin "26") (pinfunction "RXCTL/PHYAD2_26") (pintype "passive"))
    )
    (net (code "37") (name "/RXD10{slash}RXDLY") (class "Default")
      (node (ref "R514") (pin "2") (pinfunction "2_2") (pintype "passive"))
      (node (ref "R515") (pin "1") (pinfunction "1_1") (pintype "passive"))
      (node (ref "U501") (pin "25") (pinfunction "RXD0/RXDLY_25") (pintype "passive"))
    )
    (net (code "38") (name "/RXD11{slash}TXDLY") (class "Default")
      (node (ref "R512") (pin "2") (pinfunction "2_2") (pintype "passive"))
      (node (ref "R513") (pin "1") (pinfunction "1_1") (pintype "passive"))
      (node (ref "U501") (pin "24") (pinfunction "RXD1/TXDLY_24") (pintype "passive"))
    )
    (net (code "39") (name "/RXD12{slash}PLLOFF") (class "Default")
      (node (ref "R510") (pin "2") (pinfunction "2_2") (pintype "passive"))
      (node (ref "R511") (pin "1") (pinfunction "1_1") (pintype "passive"))
      (node (ref "U501") (pin "23") (pinfunction "RXD2/PLLOFF_23") (pintype "passive"))
    )
    (net (code "40") (name "/RXD13{slash}PHYAD0") (class "Default")
      (node (ref "R516") (pin "2") (pinfunction "2_2") (pintype "passive"))
      (node (ref "R517") (pin "1") (pinfunction "1_1") (pintype "passive"))
      (node (ref "U501") (pin "22") (pinfunction "RXD3/PHYAD0_22") (pintype "passive"))
    )
    (net (code "41") (name "/TCT1_0") (class "Default")
      (node (ref "C516") (pin "1") (pinfunction "1_1") (pintype "passive"))
      (node (ref "J501") (pin "12") (pinfunction "TRCT1_12") (pintype "passive"))
    )
    (net (code "42") (name "/TCT1_1") (class "Default")
      (node (ref "C517") (pin "1") (pinfunction "1_1") (pintype "passive"))
      (node (ref "J501") (pin "6") (pinfunction "TRCT2_6") (pintype "passive"))
    )
    (net (code "43") (name "/TCT1_2") (class "Default")
      (node (ref "C518") (pin "1") (pinfunction "1_1") (pintype "passive"))
      (node (ref "J501") (pin "1") (pinfunction "TRCT3_1") (pintype "passive"))
    )
    (net (code "44") (name "/TCT1_3") (class "Default")
      (node (ref "C519") (pin "1") (pinfunction "1_1") (pintype "passive"))
      (node (ref "J501") (pin "7") (pinfunction "TRCT4_7") (pintype "passive"))
    )
    (net (code "45") (name "/TS_INT") (class "Default")
      (node (ref "Q502") (pin "2") (pinfunction "S_2") (pintype "passive"))
      (node (ref "R520") (pin "1") (pinfunction "1_1") (pintype "passive"))
    )
    (net (code "46") (name "/XTAL_IN_GBE1") (class "Default")
      (node (ref "C521") (pin "1") (pinfunction "1_1") (pintype "passive"))
      (node (ref "U501") (pin "36") (pinfunction "XTAL_IN_36") (pintype "passive"))
      (node (ref "Y501") (pin "1") (pinfunction "1_1") (pintype "passive"))
    )
    (net (code "47") (name "/XTAL_OUT_GBE1") (class "Default")
      (node (ref "C522") (pin "1") (pinfunction "1_1") (pintype "passive"))
      (node (ref "U501") (pin "37") (pinfunction "XTAL_OUT/EXT_CLK_37") (pintype "passive"))
      (node (ref "Y501") (pin "3") (pinfunction "3_3") (pintype "passive"))
    )
    (net (code "48") (name "GND") (class "Default")
      (node (ref "C501") (pin "2") (pinfunction "2_2") (pintype "passive"))
      (node (ref "C502") (pin "2") (pinfunction "2_2") (pintype "passive"))
      (node (ref "C503") (pin "2") (pinfunction "2_2") (pintype "passive"))
      (node (ref "C504") (pin "2") (pinfunction "2_2") (pintype "passive"))
      (node (ref "C505") (pin "2") (pinfunction "2_2") (pintype "passive"))
      (node (ref "C506") (pin "2") (pinfunction "2_2") (pintype "passive"))
      (node (ref "C507") (pin "2") (pinfunction "2_2") (pintype "passive"))
      (node (ref "C508") (pin "2") (pinfunction "2_2") (pintype "passive"))
      (node (ref "C509") (pin "2") (pinfunction "2_2") (pintype "passive"))
      (node (ref "C510") (pin "2") (pinfunction "2_2") (pintype "passive"))
      (node (ref "C511") (pin "2") (pinfunction "2_2") (pintype "passive"))
      (node (ref "C512") (pin "2") (pinfunction "2_2") (pintype "passive"))
      (node (ref "C513") (pin "1") (pinfunction "1_1") (pintype "passive"))
      (node (ref "C514") (pin "1") (pinfunction "1_1") (pintype "passive"))
      (node (ref "C515") (pin "2") (pinfunction "2_2") (pintype "passive"))
      (node (ref "C516") (pin "2") (pinfunction "2_2") (pintype "passive"))
      (node (ref "C517") (pin "2") (pinfunction "2_2") (pintype "passive"))
      (node (ref "C518") (pin "2") (pinfunction "2_2") (pintype "passive"))
      (node (ref "C519") (pin "2") (pinfunction "2_2") (pintype "passive"))
      (node (ref "C520") (pin "2") (pinfunction "2_2") (pintype "passive"))
      (node (ref "C521") (pin "2") (pinfunction "2_2") (pintype "passive"))
      (node (ref "C522") (pin "2") (pinfunction "2_2") (pintype "passive"))
      (node (ref "C523") (pin "1") (pinfunction "1_1") (pintype "passive"))
      (node (ref "D501") (pin "3") (pinfunction "GND1_3") (pintype "passive"))
      (node (ref "D501") (pin "8") (pinfunction "GND1_8") (pintype "passive"))
      (node (ref "D502") (pin "3") (pinfunction "GND1_3") (pintype "passive"))
      (node (ref "D502") (pin "8") (pinfunction "GND1_8") (pintype "passive"))
      (node (ref "R505") (pin "2") (pinfunction "2_2") (pintype "passive"))
      (node (ref "R509") (pin "1") (pinfunction "1_1") (pintype "passive"))
      (node (ref "R510") (pin "1") (pinfunction "1_1") (pintype "passive"))
      (node (ref "R512") (pin "1") (pinfunction "1_1") (pintype "passive"))
      (node (ref "R514") (pin "1") (pinfunction "1_1") (pintype "passive"))
      (node (ref "R516") (pin "1") (pinfunction "1_1") (pintype "passive"))
      (node (ref "R518") (pin "1") (pinfunction "1_1") (pintype "passive"))
      (node (ref "R522") (pin "1") (pinfunction "1_1") (pintype "passive"))
      (node (ref "R526") (pin "1") (pinfunction "1_1") (pintype "passive"))
      (node (ref "R528") (pin "1") (pinfunction "1_1") (pintype "passive"))
      (node (ref "R530") (pin "1") (pinfunction "1_1") (pintype "passive"))
      (node (ref "U501") (pin "41") (pinfunction "EGND_41") (pintype "passive"))
      (node (ref "Y501") (pin "2") (pinfunction "GND_2") (pintype "power_in"))
      (node (ref "Y501") (pin "4") (pinfunction "GND_4") (pintype "power_in"))
    )
    (net (code "49") (name "GND_E") (class "Default")
      (node (ref "C523") (pin "2") (pinfunction "2_2") (pintype "passive"))
      (node (ref "J501") (pin "18") (pinfunction "SHIELD1_18") (pintype "passive"))
      (node (ref "J501") (pin "19") (pinfunction "SHIELD2_19") (pintype "passive"))
      (node (ref "R509") (pin "2") (pinfunction "2_2") (pintype "passive"))
    )
    (net (code "50") (name "Net-(D503-A)") (class "Default")
      (node (ref "D503") (pin "1") (pinfunction "A_1") (pintype "passive"))
      (node (ref "D504") (pin "1") (pinfunction "A_1") (pintype "passive"))
      (node (ref "D505") (pin "1") (pinfunction "A_1") (pintype "passive"))
      (node (ref "Q501") (pin "2") (pinfunction "S_2") (pintype "passive"))
      (node (ref "R524") (pin "1") (pinfunction "1_1") (pintype "passive"))
    )
    (net (code "51") (name "Net-(J501-G_CATODE)") (class "Default")
      (node (ref "J501") (pin "17") (pinfunction "G_CATODE_17") (pintype "passive"))
      (node (ref "R507") (pin "2") (pinfunction "2_2") (pintype "passive"))
    )
    (net (code "52") (name "Net-(J501-O_CATODE)") (class "Default")
      (node (ref "J501") (pin "15") (pinfunction "O_CATODE_15") (pintype "passive"))
      (node (ref "R506") (pin "2") (pinfunction "2_2") (pintype "passive"))
    )
    (net (code "53") (name "Net-(J501-Y_CATODE)") (class "Default")
      (node (ref "J501") (pin "13") (pinfunction "Y_CATODE_13") (pintype "passive"))
      (node (ref "R508") (pin "2") (pinfunction "2_2") (pintype "passive"))
    )
    (net (code "54") (name "PHY1_DVDD3V3") (class "Default")
      (node (ref "C501") (pin "1") (pinfunction "1_1") (pintype "passive"))
      (node (ref "C502") (pin "1") (pinfunction "1_1") (pintype "passive"))
      (node (ref "C520") (pin "1") (pinfunction "1_1") (pintype "passive"))
      (node (ref "FB501") (pin "2") (pinfunction "2_2") (pintype "passive"))
      (node (ref "J501") (pin "14") (pinfunction "Y_ANODE_14") (pintype "passive"))
      (node (ref "J501") (pin "16") (pinfunction "COM_ANODE_16") (pintype "passive"))
      (node (ref "R521") (pin "2") (pinfunction "2_2") (pintype "passive"))
      (node (ref "R525") (pin "2") (pinfunction "2_2") (pintype "passive"))
      (node (ref "R527") (pin "2") (pinfunction "2_2") (pintype "passive"))
      (node (ref "R529") (pin "2") (pinfunction "2_2") (pintype "passive"))
      (node (ref "R531") (pin "2") (pinfunction "2_2") (pintype "passive"))
      (node (ref "U501") (pin "29") (pinfunction "DVDD33_29_29") (pintype "power_in"))
    )
    (net (code "55") (name "PHY1_VDD1V0") (class "Default")
      (node (ref "C514") (pin "2") (pinfunction "2_2") (pintype "passive"))
      (node (ref "C515") (pin "1") (pinfunction "1_1") (pintype "passive"))
      (node (ref "FB502") (pin "2") (pinfunction "2_2") (pintype "passive"))
      (node (ref "FB503") (pin "1") (pinfunction "1_1") (pintype "passive"))
      (node (ref "L501") (pin "2") (pinfunction "2_2") (pintype "passive"))
    )
    (net (code "56") (name "PHY1_VDDIO") (class "Default")
      (node (ref "C505") (pin "1") (pinfunction "1_1") (pintype "passive"))
      (node (ref "C506") (pin "1") (pinfunction "1_1") (pintype "passive"))
      (node (ref "R501") (pin "1") (pinfunction "1_1") (pintype "passive"))
      (node (ref "R511") (pin "2") (pinfunction "2_2") (pintype "passive"))
      (node (ref "R513") (pin "2") (pinfunction "2_2") (pintype "passive"))
      (node (ref "R515") (pin "2") (pinfunction "2_2") (pintype "passive"))
      (node (ref "R517") (pin "2") (pinfunction "2_2") (pintype "passive"))
      (node (ref "R519") (pin "2") (pinfunction "2_2") (pintype "passive"))
      (node (ref "R523") (pin "2") (pinfunction "2_2") (pintype "passive"))
      (node (ref "U501") (pin "28") (pinfunction "DVDD_RG_28") (pintype "power_in"))
    )
  )
)
